# Main_uC.net
KiCad netlist of a schematic drawn in Altium Designer
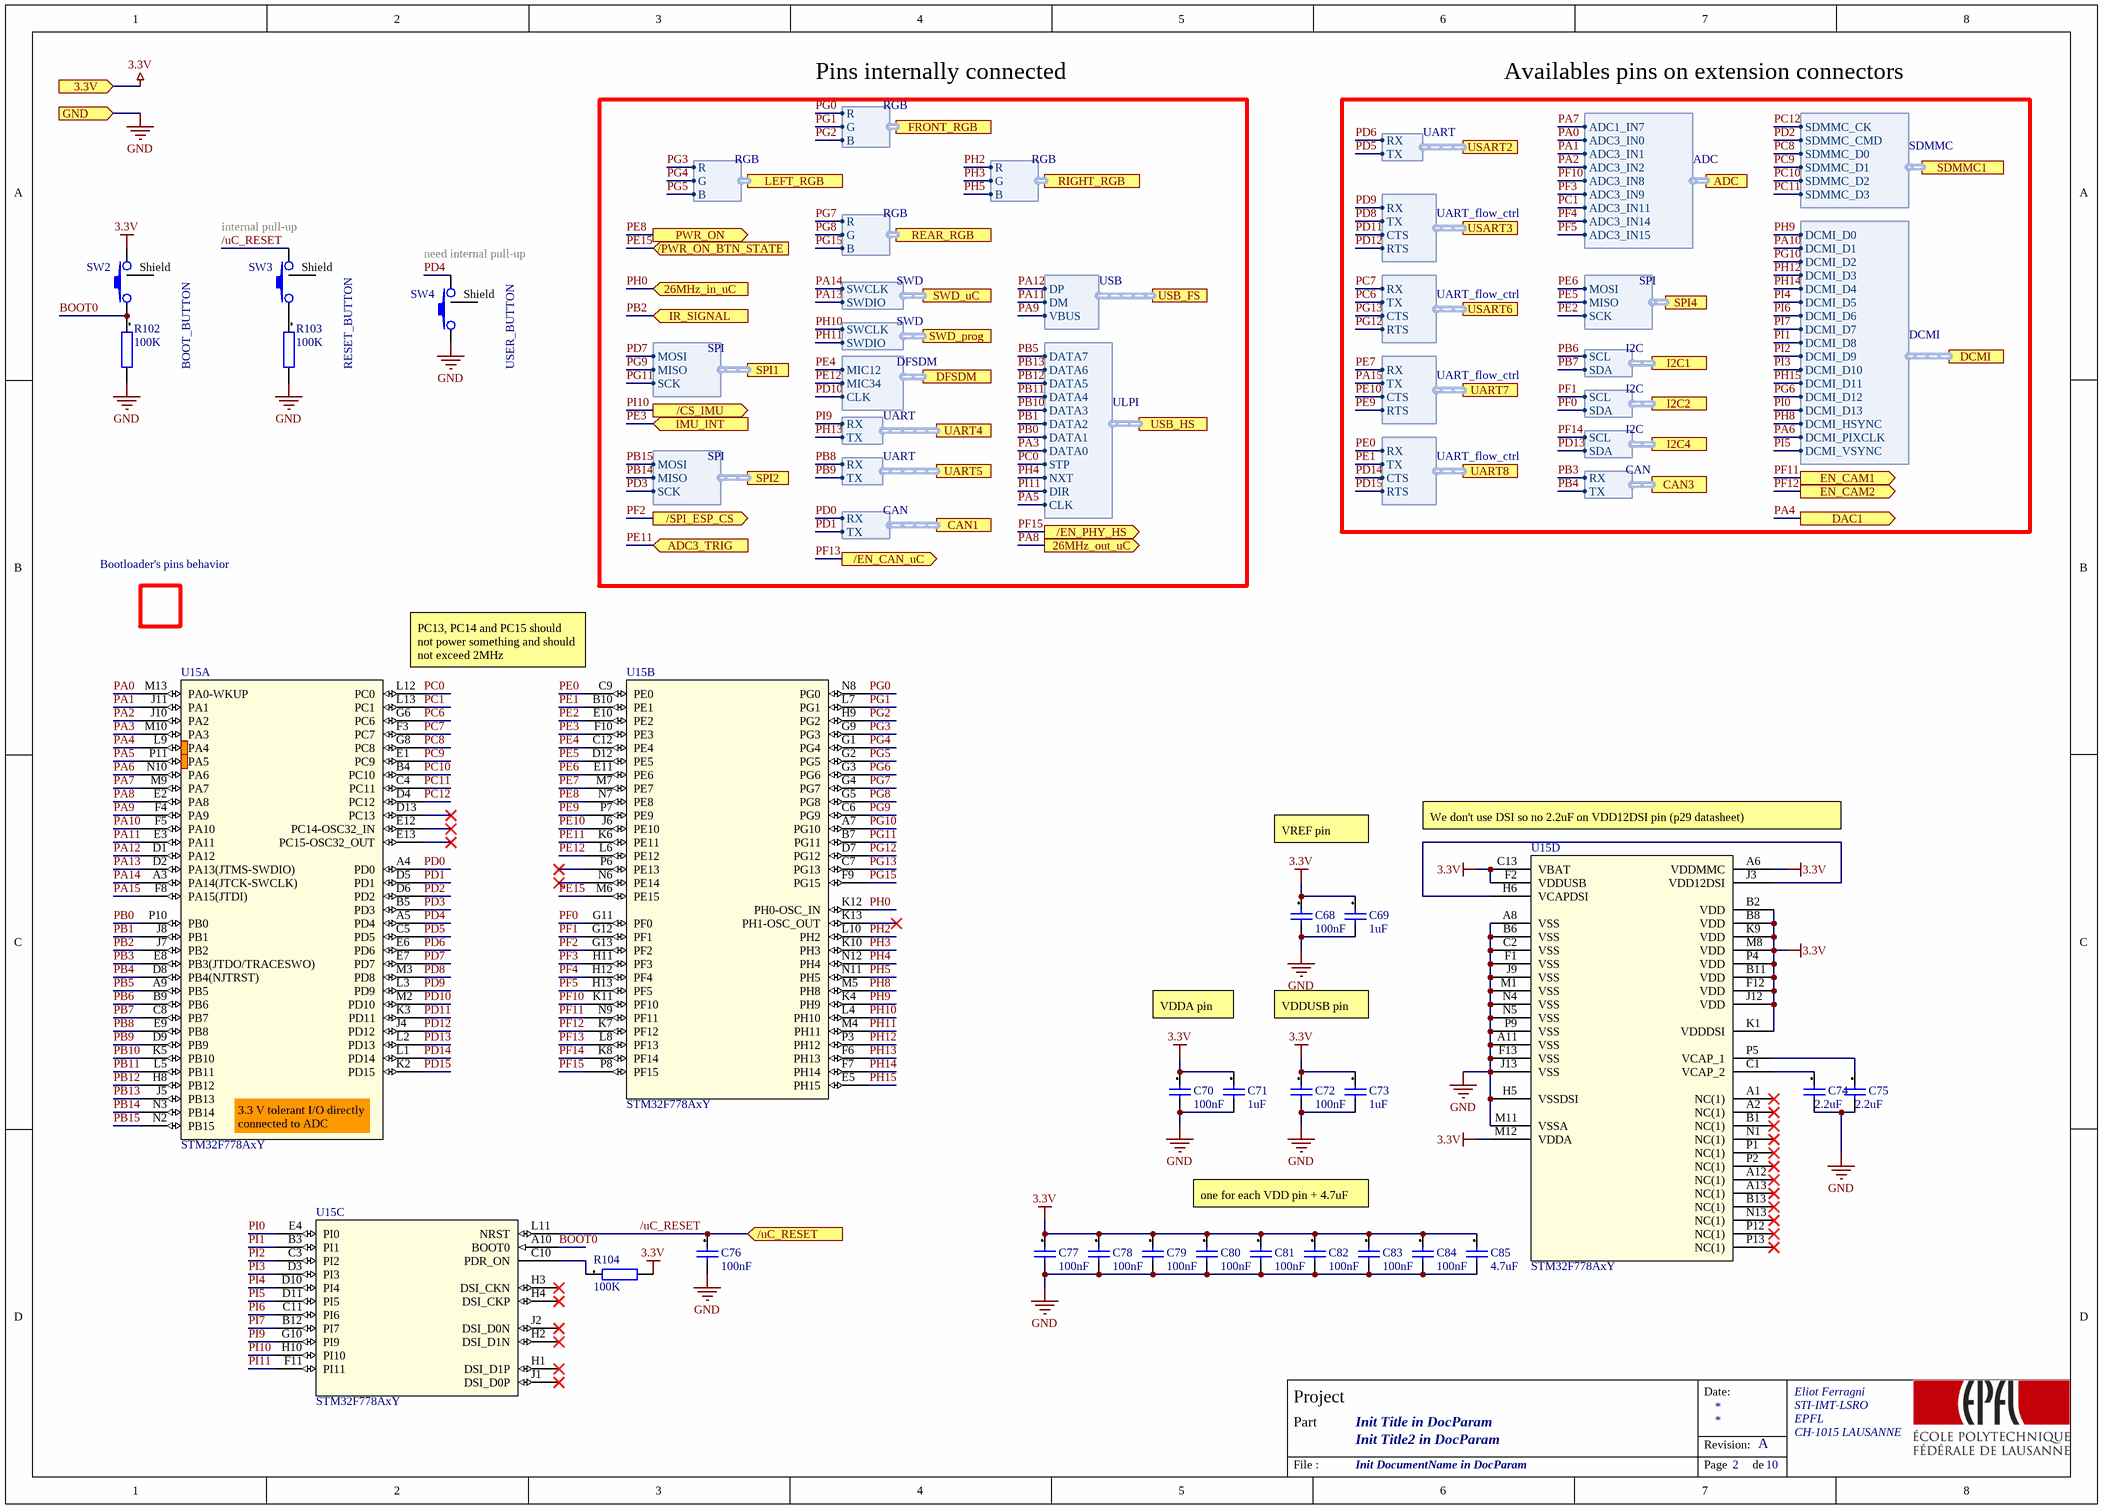
[diagram p0: Main_uC.SchDoc]

(export (version "E")
  (design (tool "Eeschema 10.0.6"))
  (components
    (comp (ref "C68")
      (value "100nF")
      (footprint "CAPC0201(0603)33_L")
      (description "Capacitor TBD 0201")
      (libsource (lib "LSRO1Altium") (part "CAP-NP"))
    )
    (comp (ref "C69")
      (value "1uF")
      (footprint "CAPC0201(0603)33_L")
      (description "Capacitor TBD 0201")
      (libsource (lib "LSRO1Altium") (part "CAP-NP"))
    )
    (comp (ref "C70")
      (value "100nF")
      (footprint "CAPC0201(0603)33_L")
      (description "Capacitor TBD 0201")
      (libsource (lib "LSRO1Altium") (part "CAP-NP"))
    )
    (comp (ref "C71")
      (value "1uF")
      (footprint "CAPC0201(0603)33_L")
      (description "Capacitor TBD 0201")
      (libsource (lib "LSRO1Altium") (part "CAP-NP"))
    )
    (comp (ref "C72")
      (value "100nF")
      (footprint "CAPC0201(0603)33_L")
      (description "Capacitor TBD 0201")
      (libsource (lib "LSRO1Altium") (part "CAP-NP"))
    )
    (comp (ref "C73")
      (value "1uF")
      (footprint "CAPC0201(0603)33_L")
      (description "Capacitor TBD 0201")
      (libsource (lib "LSRO1Altium") (part "CAP-NP"))
    )
    (comp (ref "C74")
      (value "2.2uF")
      (footprint "CAPC0201(0603)33_L")
      (description "Capacitor TBD 0201")
      (libsource (lib "LSRO1Altium") (part "CAP-NP"))
    )
    (comp (ref "C75")
      (value "2.2uF")
      (footprint "CAPC0201(0603)33_L")
      (description "Capacitor TBD 0201")
      (libsource (lib "LSRO1Altium") (part "CAP-NP"))
    )
    (comp (ref "C76")
      (value "100nF")
      (footprint "CAPC0201(0603)33_L")
      (description "Capacitor TBD 0201")
      (libsource (lib "LSRO1Altium") (part "CAP-NP"))
    )
    (comp (ref "C77")
      (value "100nF")
      (footprint "CAPC0201(0603)33_L")
      (description "Capacitor TBD 0201")
      (libsource (lib "LSRO1Altium") (part "CAP-NP"))
    )
    (comp (ref "C78")
      (value "100nF")
      (footprint "CAPC0201(0603)33_L")
      (description "Capacitor TBD 0201")
      (libsource (lib "LSRO1Altium") (part "CAP-NP"))
    )
    (comp (ref "C79")
      (value "100nF")
      (footprint "CAPC0201(0603)33_L")
      (description "Capacitor TBD 0201")
      (libsource (lib "LSRO1Altium") (part "CAP-NP"))
    )
    (comp (ref "C80")
      (value "100nF")
      (footprint "CAPC0201(0603)33_L")
      (description "Capacitor TBD 0201")
      (libsource (lib "LSRO1Altium") (part "CAP-NP"))
    )
    (comp (ref "C81")
      (value "100nF")
      (footprint "CAPC0201(0603)33_L")
      (description "Capacitor TBD 0201")
      (libsource (lib "LSRO1Altium") (part "CAP-NP"))
    )
    (comp (ref "C82")
      (value "100nF")
      (footprint "CAPC0201(0603)33_L")
      (description "Capacitor TBD 0201")
      (libsource (lib "LSRO1Altium") (part "CAP-NP"))
    )
    (comp (ref "C83")
      (value "100nF")
      (footprint "CAPC0201(0603)33_L")
      (description "Capacitor TBD 0201")
      (libsource (lib "LSRO1Altium") (part "CAP-NP"))
    )
    (comp (ref "C84")
      (value "100nF")
      (footprint "CAPC0201(0603)33_L")
      (description "Capacitor TBD 0201")
      (libsource (lib "LSRO1Altium") (part "CAP-NP"))
    )
    (comp (ref "C85")
      (value "4.7uF")
      (footprint "CAPC0201(0603)33_L")
      (description "Capacitor TBD 0201")
      (libsource (lib "LSRO1Altium") (part "CAP-NP"))
    )
    (comp (ref "R102")
      (value "100K")
      (footprint "RESC0201(0603)_L")
      (description "Resistor ToDo 0201")
      (libsource (lib "LSRO1Altium") (part "RES"))
    )
    (comp (ref "R103")
      (value "100K")
      (footprint "RESC0201(0603)_L")
      (description "Resistor ToDo 0201")
      (libsource (lib "LSRO1Altium") (part "RES"))
    )
    (comp (ref "R104")
      (value "100K")
      (footprint "RESC0201(0603)_L")
      (description "Resistor ToDo 0201")
      (libsource (lib "LSRO1Altium") (part "RES"))
    )
    (comp (ref "SW2")
      (value "button")
      (footprint "C&K_KMR2")
      (description "KMR221GLFS")
      (fields (field (name "MANUFACTURER") "Tyco"))
      (libsource (lib "Schlib") (part "C&K KMR2"))
    )
    (comp (ref "SW3")
      (value "button")
      (footprint "C&K_KMR2")
      (description "KMR221GLFS")
      (fields (field (name "MANUFACTURER") "Tyco"))
      (libsource (lib "Schlib") (part "C&K KMR2"))
    )
    (comp (ref "SW4")
      (value "button")
      (footprint "C&K_KMR2")
      (description "KMR221GLFS")
      (fields (field (name "MANUFACTURER") "Tyco"))
      (libsource (lib "Schlib") (part "C&K KMR2"))
    )
    (comp (ref "U15")
      (value "STM32F778AxY")
      (footprint "WLCSP-180")
      (description "Imported")
      (fields
        (field (name "MANUFACTURER_PART_NUMBER") "stm32f77xaxy")
        (field (name "COPYRIGHT") "Copyright (C) 2016 Accelerated Designs. All rights reserved")
      )
      (libsource (lib "Schlib") (part "STM32F77XAXY"))
    )
  )
  (nets
    (net (code "14") (name "/BOOT0") (class "Default")
      (node (ref "R102") (pin "1") (pinfunction "1_1") (pintype "passive"))
      (node (ref "SW2") (pin "1") (pintype "passive"))
      (node (ref "U15") (pin "A10") (pinfunction "BOOT0_A10") (pintype "input"))
    )
    (net (code "16") (name "/PA0") (class "Default")
      (node (ref "U15") (pin "M13") (pinfunction "PA0-WKUP_M13") (pintype "bidirectional"))
    )
    (net (code "17") (name "/PA1") (class "Default")
      (node (ref "U15") (pin "J11") (pinfunction "PA1_J11") (pintype "bidirectional"))
    )
    (net (code "18") (name "/PA2") (class "Default")
      (node (ref "U15") (pin "J10") (pinfunction "PA2_J10") (pintype "bidirectional"))
    )
    (net (code "19") (name "/PA3") (class "Default")
      (node (ref "U15") (pin "M10") (pinfunction "PA3_M10") (pintype "bidirectional"))
    )
    (net (code "20") (name "/PA4") (class "Default")
      (node (ref "U15") (pin "L9") (pinfunction "PA4_L9") (pintype "bidirectional"))
    )
    (net (code "21") (name "/PA5") (class "Default")
      (node (ref "U15") (pin "P11") (pinfunction "PA5_P11") (pintype "bidirectional"))
    )
    (net (code "22") (name "/PA6") (class "Default")
      (node (ref "U15") (pin "N10") (pinfunction "PA6_N10") (pintype "bidirectional"))
    )
    (net (code "23") (name "/PA7") (class "Default")
      (node (ref "U15") (pin "M9") (pinfunction "PA7_M9") (pintype "bidirectional"))
    )
    (net (code "24") (name "/PA8") (class "Default")
      (node (ref "U15") (pin "E2") (pinfunction "PA8_E2") (pintype "bidirectional"))
    )
    (net (code "25") (name "/PA9") (class "Default")
      (node (ref "U15") (pin "F4") (pinfunction "PA9_F4") (pintype "bidirectional"))
    )
    (net (code "26") (name "/PA10") (class "Default")
      (node (ref "U15") (pin "F5") (pinfunction "PA10_F5") (pintype "bidirectional"))
    )
    (net (code "27") (name "/PA11") (class "Default")
      (node (ref "U15") (pin "E3") (pinfunction "PA11_E3") (pintype "bidirectional"))
    )
    (net (code "28") (name "/PA12") (class "Default")
      (node (ref "U15") (pin "D1") (pinfunction "PA12_D1") (pintype "bidirectional"))
    )
    (net (code "29") (name "/PA13") (class "Default")
      (node (ref "U15") (pin "D2") (pinfunction "PA13(JTMS-SWDIO)_D2") (pintype "bidirectional"))
    )
    (net (code "30") (name "/PA14") (class "Default")
      (node (ref "U15") (pin "A3") (pinfunction "PA14(JTCK-SWCLK)_A3") (pintype "bidirectional"))
    )
    (net (code "31") (name "/PA15") (class "Default")
      (node (ref "U15") (pin "F8") (pinfunction "PA15(JTDI)_F8") (pintype "bidirectional"))
    )
    (net (code "32") (name "/PB0") (class "Default")
      (node (ref "U15") (pin "P10") (pinfunction "PB0_P10") (pintype "bidirectional"))
    )
    (net (code "33") (name "/PB1") (class "Default")
      (node (ref "U15") (pin "J8") (pinfunction "PB1_J8") (pintype "bidirectional"))
    )
    (net (code "34") (name "/PB2") (class "Default")
      (node (ref "U15") (pin "J7") (pinfunction "PB2_J7") (pintype "bidirectional"))
    )
    (net (code "35") (name "/PB3") (class "Default")
      (node (ref "U15") (pin "E8") (pinfunction "PB3(JTDO/TRACESWO)_E8") (pintype "bidirectional"))
    )
    (net (code "36") (name "/PB4") (class "Default")
      (node (ref "U15") (pin "D8") (pinfunction "PB4(NJTRST)_D8") (pintype "bidirectional"))
    )
    (net (code "37") (name "/PB5") (class "Default")
      (node (ref "U15") (pin "A9") (pinfunction "PB5_A9") (pintype "bidirectional"))
    )
    (net (code "38") (name "/PB6") (class "Default")
      (node (ref "U15") (pin "B9") (pinfunction "PB6_B9") (pintype "bidirectional"))
    )
    (net (code "39") (name "/PB7") (class "Default")
      (node (ref "U15") (pin "C8") (pinfunction "PB7_C8") (pintype "bidirectional"))
    )
    (net (code "40") (name "/PB8") (class "Default")
      (node (ref "U15") (pin "E9") (pinfunction "PB8_E9") (pintype "bidirectional"))
    )
    (net (code "41") (name "/PB9") (class "Default")
      (node (ref "U15") (pin "D9") (pinfunction "PB9_D9") (pintype "bidirectional"))
    )
    (net (code "42") (name "/PB10") (class "Default")
      (node (ref "U15") (pin "K5") (pinfunction "PB10_K5") (pintype "bidirectional"))
    )
    (net (code "43") (name "/PB11") (class "Default")
      (node (ref "U15") (pin "L5") (pinfunction "PB11_L5") (pintype "bidirectional"))
    )
    (net (code "44") (name "/PB12") (class "Default")
      (node (ref "U15") (pin "H8") (pinfunction "PB12_H8") (pintype "bidirectional"))
    )
    (net (code "45") (name "/PB13") (class "Default")
      (node (ref "U15") (pin "J5") (pinfunction "PB13_J5") (pintype "bidirectional"))
    )
    (net (code "46") (name "/PB14") (class "Default")
      (node (ref "U15") (pin "N3") (pinfunction "PB14_N3") (pintype "bidirectional"))
    )
    (net (code "47") (name "/PB15") (class "Default")
      (node (ref "U15") (pin "N2") (pinfunction "PB15_N2") (pintype "bidirectional"))
    )
    (net (code "48") (name "/PC0") (class "Default")
      (node (ref "U15") (pin "L12") (pinfunction "PC0_L12") (pintype "bidirectional"))
    )
    (net (code "49") (name "/PC1") (class "Default")
      (node (ref "U15") (pin "L13") (pinfunction "PC1_L13") (pintype "bidirectional"))
    )
    (net (code "50") (name "/PC6") (class "Default")
      (node (ref "U15") (pin "G6") (pinfunction "PC6_G6") (pintype "bidirectional"))
    )
    (net (code "51") (name "/PC7") (class "Default")
      (node (ref "U15") (pin "F3") (pinfunction "PC7_F3") (pintype "bidirectional"))
    )
    (net (code "52") (name "/PC8") (class "Default")
      (node (ref "U15") (pin "G8") (pinfunction "PC8_G8") (pintype "bidirectional"))
    )
    (net (code "53") (name "/PC9") (class "Default")
      (node (ref "U15") (pin "E1") (pinfunction "PC9_E1") (pintype "bidirectional"))
    )
    (net (code "54") (name "/PC10") (class "Default")
      (node (ref "U15") (pin "B4") (pinfunction "PC10_B4") (pintype "bidirectional"))
    )
    (net (code "55") (name "/PC11") (class "Default")
      (node (ref "U15") (pin "C4") (pinfunction "PC11_C4") (pintype "bidirectional"))
    )
    (net (code "56") (name "/PC12") (class "Default")
      (node (ref "U15") (pin "D4") (pinfunction "PC12_D4") (pintype "bidirectional"))
    )
    (net (code "57") (name "/PD0") (class "Default")
      (node (ref "U15") (pin "A4") (pinfunction "PD0_A4") (pintype "bidirectional"))
    )
    (net (code "58") (name "/PD1") (class "Default")
      (node (ref "U15") (pin "D5") (pinfunction "PD1_D5") (pintype "bidirectional"))
    )
    (net (code "59") (name "/PD2") (class "Default")
      (node (ref "U15") (pin "D6") (pinfunction "PD2_D6") (pintype "bidirectional"))
    )
    (net (code "60") (name "/PD3") (class "Default")
      (node (ref "U15") (pin "B5") (pinfunction "PD3_B5") (pintype "bidirectional"))
    )
    (net (code "61") (name "/PD4") (class "Default")
      (node (ref "SW4") (pin "2") (pintype "passive"))
      (node (ref "U15") (pin "A5") (pinfunction "PD4_A5") (pintype "bidirectional"))
    )
    (net (code "62") (name "/PD5") (class "Default")
      (node (ref "U15") (pin "C5") (pinfunction "PD5_C5") (pintype "bidirectional"))
    )
    (net (code "63") (name "/PD6") (class "Default")
      (node (ref "U15") (pin "E6") (pinfunction "PD6_E6") (pintype "bidirectional"))
    )
    (net (code "64") (name "/PD7") (class "Default")
      (node (ref "U15") (pin "E7") (pinfunction "PD7_E7") (pintype "bidirectional"))
    )
    (net (code "65") (name "/PD8") (class "Default")
      (node (ref "U15") (pin "M3") (pinfunction "PD8_M3") (pintype "bidirectional"))
    )
    (net (code "66") (name "/PD9") (class "Default")
      (node (ref "U15") (pin "L3") (pinfunction "PD9_L3") (pintype "bidirectional"))
    )
    (net (code "67") (name "/PD10") (class "Default")
      (node (ref "U15") (pin "M2") (pinfunction "PD10_M2") (pintype "bidirectional"))
    )
    (net (code "68") (name "/PD11") (class "Default")
      (node (ref "U15") (pin "K3") (pinfunction "PD11_K3") (pintype "bidirectional"))
    )
    (net (code "69") (name "/PD12") (class "Default")
      (node (ref "U15") (pin "J4") (pinfunction "PD12_J4") (pintype "bidirectional"))
    )
    (net (code "70") (name "/PD13") (class "Default")
      (node (ref "U15") (pin "L2") (pinfunction "PD13_L2") (pintype "bidirectional"))
    )
    (net (code "71") (name "/PD14") (class "Default")
      (node (ref "U15") (pin "L1") (pinfunction "PD14_L1") (pintype "bidirectional"))
    )
    (net (code "72") (name "/PD15") (class "Default")
      (node (ref "U15") (pin "K2") (pinfunction "PD15_K2") (pintype "bidirectional"))
    )
    (net (code "73") (name "/PE0") (class "Default")
      (node (ref "U15") (pin "C9") (pinfunction "PE0_C9") (pintype "bidirectional"))
    )
    (net (code "74") (name "/PE1") (class "Default")
      (node (ref "U15") (pin "B10") (pinfunction "PE1_B10") (pintype "bidirectional"))
    )
    (net (code "75") (name "/PE2") (class "Default")
      (node (ref "U15") (pin "E10") (pinfunction "PE2_E10") (pintype "bidirectional"))
    )
    (net (code "76") (name "/PE3") (class "Default")
      (node (ref "U15") (pin "F10") (pinfunction "PE3_F10") (pintype "bidirectional"))
    )
    (net (code "77") (name "/PE4") (class "Default")
      (node (ref "U15") (pin "C12") (pinfunction "PE4_C12") (pintype "bidirectional"))
    )
    (net (code "78") (name "/PE5") (class "Default")
      (node (ref "U15") (pin "D12") (pinfunction "PE5_D12") (pintype "bidirectional"))
    )
    (net (code "79") (name "/PE6") (class "Default")
      (node (ref "U15") (pin "E11") (pinfunction "PE6_E11") (pintype "bidirectional"))
    )
    (net (code "80") (name "/PE7") (class "Default")
      (node (ref "U15") (pin "M7") (pinfunction "PE7_M7") (pintype "bidirectional"))
    )
    (net (code "81") (name "/PE8") (class "Default")
      (node (ref "U15") (pin "N7") (pinfunction "PE8_N7") (pintype "bidirectional"))
    )
    (net (code "82") (name "/PE9") (class "Default")
      (node (ref "U15") (pin "P7") (pinfunction "PE9_P7") (pintype "bidirectional"))
    )
    (net (code "83") (name "/PE10") (class "Default")
      (node (ref "U15") (pin "J6") (pinfunction "PE10_J6") (pintype "bidirectional"))
    )
    (net (code "84") (name "/PE11") (class "Default")
      (node (ref "U15") (pin "K6") (pinfunction "PE11_K6") (pintype "bidirectional"))
    )
    (net (code "85") (name "/PE12") (class "Default")
      (node (ref "U15") (pin "L6") (pinfunction "PE12_L6") (pintype "bidirectional"))
    )
    (net (code "86") (name "/PE15") (class "Default")
      (node (ref "U15") (pin "M6") (pinfunction "PE15_M6") (pintype "bidirectional"))
    )
    (net (code "87") (name "/PF0") (class "Default")
      (node (ref "U15") (pin "G11") (pinfunction "PF0_G11") (pintype "bidirectional"))
    )
    (net (code "88") (name "/PF1") (class "Default")
      (node (ref "U15") (pin "G12") (pinfunction "PF1_G12") (pintype "bidirectional"))
    )
    (net (code "89") (name "/PF2") (class "Default")
      (node (ref "U15") (pin "G13") (pinfunction "PF2_G13") (pintype "bidirectional"))
    )
    (net (code "90") (name "/PF3") (class "Default")
      (node (ref "U15") (pin "H11") (pinfunction "PF3_H11") (pintype "bidirectional"))
    )
    (net (code "91") (name "/PF4") (class "Default")
      (node (ref "U15") (pin "H12") (pinfunction "PF4_H12") (pintype "bidirectional"))
    )
    (net (code "92") (name "/PF5") (class "Default")
      (node (ref "U15") (pin "H13") (pinfunction "PF5_H13") (pintype "bidirectional"))
    )
    (net (code "93") (name "/PF10") (class "Default")
      (node (ref "U15") (pin "K11") (pinfunction "PF10_K11") (pintype "bidirectional"))
    )
    (net (code "94") (name "/PF11") (class "Default")
      (node (ref "U15") (pin "N9") (pinfunction "PF11_N9") (pintype "bidirectional"))
    )
    (net (code "95") (name "/PF12") (class "Default")
      (node (ref "U15") (pin "K7") (pinfunction "PF12_K7") (pintype "bidirectional"))
    )
    (net (code "96") (name "/PF13") (class "Default")
      (node (ref "U15") (pin "L8") (pinfunction "PF13_L8") (pintype "bidirectional"))
    )
    (net (code "97") (name "/PF14") (class "Default")
      (node (ref "U15") (pin "K8") (pinfunction "PF14_K8") (pintype "bidirectional"))
    )
    (net (code "98") (name "/PF15") (class "Default")
      (node (ref "U15") (pin "P8") (pinfunction "PF15_P8") (pintype "bidirectional"))
    )
    (net (code "99") (name "/PG0") (class "Default")
      (node (ref "U15") (pin "N8") (pinfunction "PG0_N8") (pintype "bidirectional"))
    )
    (net (code "100") (name "/PG1") (class "Default")
      (node (ref "U15") (pin "L7") (pinfunction "PG1_L7") (pintype "bidirectional"))
    )
    (net (code "101") (name "/PG2") (class "Default")
      (node (ref "U15") (pin "H9") (pinfunction "PG2_H9") (pintype "bidirectional"))
    )
    (net (code "102") (name "/PG3") (class "Default")
      (node (ref "U15") (pin "G9") (pinfunction "PG3_G9") (pintype "bidirectional"))
    )
    (net (code "103") (name "/PG4") (class "Default")
      (node (ref "U15") (pin "G1") (pinfunction "PG4_G1") (pintype "bidirectional"))
    )
    (net (code "104") (name "/PG5") (class "Default")
      (node (ref "U15") (pin "G2") (pinfunction "PG5_G2") (pintype "bidirectional"))
    )
    (net (code "105") (name "/PG6") (class "Default")
      (node (ref "U15") (pin "G3") (pinfunction "PG6_G3") (pintype "bidirectional"))
    )
    (net (code "106") (name "/PG7") (class "Default")
      (node (ref "U15") (pin "G4") (pinfunction "PG7_G4") (pintype "bidirectional"))
    )
    (net (code "107") (name "/PG8") (class "Default")
      (node (ref "U15") (pin "G5") (pinfunction "PG8_G5") (pintype "bidirectional"))
    )
    (net (code "108") (name "/PG9") (class "Default")
      (node (ref "U15") (pin "C6") (pinfunction "PG9_C6") (pintype "bidirectional"))
    )
    (net (code "109") (name "/PG10") (class "Default")
      (node (ref "U15") (pin "A7") (pinfunction "PG10_A7") (pintype "bidirectional"))
    )
    (net (code "110") (name "/PG11") (class "Default")
      (node (ref "U15") (pin "B7") (pinfunction "PG11_B7") (pintype "bidirectional"))
    )
    (net (code "111") (name "/PG12") (class "Default")
      (node (ref "U15") (pin "D7") (pinfunction "PG12_D7") (pintype "bidirectional"))
    )
    (net (code "112") (name "/PG13") (class "Default")
      (node (ref "U15") (pin "C7") (pinfunction "PG13_C7") (pintype "bidirectional"))
    )
    (net (code "113") (name "/PG15") (class "Default")
      (node (ref "U15") (pin "F9") (pinfunction "PG15_F9") (pintype "bidirectional"))
    )
    (net (code "114") (name "/PH0") (class "Default")
      (node (ref "U15") (pin "K12") (pinfunction "PH0-OSC_IN_K12") (pintype "bidirectional"))
    )
    (net (code "115") (name "/PH2") (class "Default")
      (node (ref "U15") (pin "L10") (pinfunction "PH2_L10") (pintype "bidirectional"))
    )
    (net (code "116") (name "/PH3") (class "Default")
      (node (ref "U15") (pin "K10") (pinfunction "PH3_K10") (pintype "bidirectional"))
    )
    (net (code "117") (name "/PH4") (class "Default")
      (node (ref "U15") (pin "N12") (pinfunction "PH4_N12") (pintype "bidirectional"))
    )
    (net (code "118") (name "/PH5") (class "Default")
      (node (ref "U15") (pin "N11") (pinfunction "PH5_N11") (pintype "bidirectional"))
    )
    (net (code "119") (name "/PH8") (class "Default")
      (node (ref "U15") (pin "M5") (pinfunction "PH8_M5") (pintype "bidirectional"))
    )
    (net (code "120") (name "/PH9") (class "Default")
      (node (ref "U15") (pin "K4") (pinfunction "PH9_K4") (pintype "bidirectional"))
    )
    (net (code "121") (name "/PH10") (class "Default")
      (node (ref "U15") (pin "L4") (pinfunction "PH10_L4") (pintype "bidirectional"))
    )
    (net (code "122") (name "/PH11") (class "Default")
      (node (ref "U15") (pin "M4") (pinfunction "PH11_M4") (pintype "bidirectional"))
    )
    (net (code "123") (name "/PH12") (class "Default")
      (node (ref "U15") (pin "P3") (pinfunction "PH12_P3") (pintype "bidirectional"))
    )
    (net (code "124") (name "/PH13") (class "Default")
      (node (ref "U15") (pin "F6") (pinfunction "PH13_F6") (pintype "bidirectional"))
    )
    (net (code "125") (name "/PH14") (class "Default")
      (node (ref "U15") (pin "F7") (pinfunction "PH14_F7") (pintype "bidirectional"))
    )
    (net (code "126") (name "/PH15") (class "Default")
      (node (ref "U15") (pin "E5") (pinfunction "PH15_E5") (pintype "bidirectional"))
    )
    (net (code "127") (name "/PI0") (class "Default")
      (node (ref "U15") (pin "E4") (pinfunction "PI0_E4") (pintype "bidirectional"))
    )
    (net (code "128") (name "/PI1") (class "Default")
      (node (ref "U15") (pin "B3") (pinfunction "PI1_B3") (pintype "bidirectional"))
    )
    (net (code "129") (name "/PI2") (class "Default")
      (node (ref "U15") (pin "C3") (pinfunction "PI2_C3") (pintype "bidirectional"))
    )
    (net (code "130") (name "/PI3") (class "Default")
      (node (ref "U15") (pin "D3") (pinfunction "PI3_D3") (pintype "bidirectional"))
    )
    (net (code "131") (name "/PI4") (class "Default")
      (node (ref "U15") (pin "D10") (pinfunction "PI4_D10") (pintype "bidirectional"))
    )
    (net (code "132") (name "/PI5") (class "Default")
      (node (ref "U15") (pin "D11") (pinfunction "PI5_D11") (pintype "bidirectional"))
    )
    (net (code "133") (name "/PI6") (class "Default")
      (node (ref "U15") (pin "C11") (pinfunction "PI6_C11") (pintype "bidirectional"))
    )
    (net (code "134") (name "/PI7") (class "Default")
      (node (ref "U15") (pin "B12") (pinfunction "PI7_B12") (pintype "bidirectional"))
    )
    (net (code "135") (name "/PI9") (class "Default")
      (node (ref "U15") (pin "G10") (pinfunction "PI9_G10") (pintype "bidirectional"))
    )
    (net (code "136") (name "/PI10") (class "Default")
      (node (ref "U15") (pin "H10") (pinfunction "PI10_H10") (pintype "bidirectional"))
    )
    (net (code "137") (name "/PI11") (class "Default")
      (node (ref "U15") (pin "F11") (pinfunction "PI11_F11") (pintype "bidirectional"))
    )
    (net (code "150") (name "/{slash}uC_RESET") (class "Default")
      (node (ref "C76") (pin "1") (pinfunction "1_1") (pintype "passive"))
      (node (ref "SW3") (pin "2") (pintype "passive"))
      (node (ref "U15") (pin "L11") (pinfunction "NRST_L11") (pintype "bidirectional"))
    )
    (net (code "151") (name "3.3V") (class "Default")
      (node (ref "C68") (pin "1") (pinfunction "1_1") (pintype "passive"))
      (node (ref "C69") (pin "1") (pinfunction "1_1") (pintype "passive"))
      (node (ref "C70") (pin "1") (pinfunction "1_1") (pintype "passive"))
      (node (ref "C71") (pin "1") (pinfunction "1_1") (pintype "passive"))
      (node (ref "C72") (pin "1") (pinfunction "1_1") (pintype "passive"))
      (node (ref "C73") (pin "1") (pinfunction "1_1") (pintype "passive"))
      (node (ref "C77") (pin "1") (pinfunction "1_1") (pintype "passive"))
      (node (ref "C78") (pin "1") (pinfunction "1_1") (pintype "passive"))
      (node (ref "C79") (pin "1") (pinfunction "1_1") (pintype "passive"))
      (node (ref "C80") (pin "1") (pinfunction "1_1") (pintype "passive"))
      (node (ref "C81") (pin "1") (pinfunction "1_1") (pintype "passive"))
      (node (ref "C82") (pin "1") (pinfunction "1_1") (pintype "passive"))
      (node (ref "C83") (pin "1") (pinfunction "1_1") (pintype "passive"))
      (node (ref "C84") (pin "1") (pinfunction "1_1") (pintype "passive"))
      (node (ref "C85") (pin "1") (pinfunction "1_1") (pintype "passive"))
      (node (ref "R104") (pin "2") (pinfunction "2_2") (pintype "passive"))
      (node (ref "SW2") (pin "2") (pintype "passive"))
      (node (ref "U15") (pin "A6") (pinfunction "VDDMMC_A6") (pintype "power_in"))
      (node (ref "U15") (pin "B11") (pinfunction "VDD_B11") (pintype "power_in"))
      (node (ref "U15") (pin "B2") (pinfunction "VDD_B2") (pintype "power_in"))
      (node (ref "U15") (pin "B8") (pinfunction "VDD_B8") (pintype "power_in"))
      (node (ref "U15") (pin "C13") (pinfunction "VBAT_C13") (pintype "power_in"))
      (node (ref "U15") (pin "F12") (pinfunction "VDD_F12") (pintype "power_in"))
      (node (ref "U15") (pin "F2") (pinfunction "VDDUSB_F2") (pintype "power_in"))
      (node (ref "U15") (pin "J12") (pinfunction "VDD_J12") (pintype "power_in"))
      (node (ref "U15") (pin "K1") (pinfunction "VDDDSI_K1") (pintype "power_in"))
      (node (ref "U15") (pin "K9") (pinfunction "VDD_K9") (pintype "power_in"))
      (node (ref "U15") (pin "M12") (pinfunction "VDDA_M12") (pintype "power_in"))
      (node (ref "U15") (pin "M8") (pinfunction "VDD_M8") (pintype "power_in"))
      (node (ref "U15") (pin "P4") (pinfunction "VDD_P4") (pintype "power_in"))
    )
    (net (code "152") (name "GND") (class "Default")
      (node (ref "C68") (pin "2") (pinfunction "2_2") (pintype "passive"))
      (node (ref "C69") (pin "2") (pinfunction "2_2") (pintype "passive"))
      (node (ref "C70") (pin "2") (pinfunction "2_2") (pintype "passive"))
      (node (ref "C71") (pin "2") (pinfunction "2_2") (pintype "passive"))
      (node (ref "C72") (pin "2") (pinfunction "2_2") (pintype "passive"))
      (node (ref "C73") (pin "2") (pinfunction "2_2") (pintype "passive"))
      (node (ref "C74") (pin "2") (pinfunction "2_2") (pintype "passive"))
      (node (ref "C75") (pin "2") (pinfunction "2_2") (pintype "passive"))
      (node (ref "C76") (pin "2") (pinfunction "2_2") (pintype "passive"))
      (node (ref "C77") (pin "2") (pinfunction "2_2") (pintype "passive"))
      (node (ref "C78") (pin "2") (pinfunction "2_2") (pintype "passive"))
      (node (ref "C79") (pin "2") (pinfunction "2_2") (pintype "passive"))
      (node (ref "C80") (pin "2") (pinfunction "2_2") (pintype "passive"))
      (node (ref "C81") (pin "2") (pinfunction "2_2") (pintype "passive"))
      (node (ref "C82") (pin "2") (pinfunction "2_2") (pintype "passive"))
      (node (ref "C83") (pin "2") (pinfunction "2_2") (pintype "passive"))
      (node (ref "C84") (pin "2") (pinfunction "2_2") (pintype "passive"))
      (node (ref "C85") (pin "2") (pinfunction "2_2") (pintype "passive"))
      (node (ref "R102") (pin "2") (pinfunction "2_2") (pintype "passive"))
      (node (ref "R103") (pin "2") (pinfunction "2_2") (pintype "passive"))
      (node (ref "SW4") (pin "1") (pintype "passive"))
      (node (ref "U15") (pin "A11") (pinfunction "VSS_A11") (pintype "power_in"))
      (node (ref "U15") (pin "A8") (pinfunction "VSS_A8") (pintype "power_in"))
      (node (ref "U15") (pin "B6") (pinfunction "VSS_B6") (pintype "power_in"))
      (node (ref "U15") (pin "C2") (pinfunction "VSS_C2") (pintype "power_in"))
      (node (ref "U15") (pin "F1") (pinfunction "VSS_F1") (pintype "power_in"))
      (node (ref "U15") (pin "F13") (pinfunction "VSS_F13") (pintype "power_in"))
      (node (ref "U15") (pin "H5") (pinfunction "VSSDSI_H5") (pintype "power_in"))
      (node (ref "U15") (pin "J13") (pinfunction "VSS_J13") (pintype "power_in"))
      (node (ref "U15") (pin "J9") (pinfunction "VSS_J9") (pintype "power_in"))
      (node (ref "U15") (pin "M1") (pinfunction "VSS_M1") (pintype "power_in"))
      (node (ref "U15") (pin "M11") (pinfunction "VSSA_M11") (pintype "power_in"))
      (node (ref "U15") (pin "N4") (pinfunction "VSS_N4") (pintype "power_in"))
      (node (ref "U15") (pin "N5") (pinfunction "VSS_N5") (pintype "power_in"))
      (node (ref "U15") (pin "P9") (pinfunction "VSS_P9") (pintype "power_in"))
    )
    (net (code "153") (name "Net-(R103-Pad1)") (class "Default")
      (node (ref "R103") (pin "1") (pinfunction "1_1") (pintype "passive"))
      (node (ref "SW3") (pin "1") (pintype "passive"))
    )
    (net (code "154") (name "Net-(U15C-PDR_ON)") (class "Default")
      (node (ref "R104") (pin "1") (pinfunction "1_1") (pintype "passive"))
      (node (ref "U15") (pin "C10") (pinfunction "PDR_ON_C10") (pintype "passive"))
    )
    (net (code "155") (name "Net-(U15D-VCAPDSI)") (class "Default")
      (node (ref "U15") (pin "H6") (pinfunction "VCAPDSI_H6") (pintype "power_in"))
      (node (ref "U15") (pin "J3") (pinfunction "VDD12DSI_J3") (pintype "power_in"))
    )
    (net (code "156") (name "Net-(U15D-VCAP_1)") (class "Default")
      (node (ref "C75") (pin "1") (pinfunction "1_1") (pintype "passive"))
      (node (ref "U15") (pin "P5") (pinfunction "VCAP_1_P5") (pintype "power_in"))
    )
    (net (code "157") (name "Net-(U15D-VCAP_2)") (class "Default")
      (node (ref "C74") (pin "1") (pinfunction "1_1") (pintype "passive"))
      (node (ref "U15") (pin "C1") (pinfunction "VCAP_2_C1") (pintype "power_in"))
    )
    (net (code "158") (name "unconnected-(SW2-PadShield)") (class "Default")
      (node (ref "SW2") (pin "Shield") (pinfunction "Shield_Shield") (pintype "passive"))
    )
    (net (code "159") (name "unconnected-(SW3-PadShield)") (class "Default")
      (node (ref "SW3") (pin "Shield") (pinfunction "Shield_Shield") (pintype "passive"))
    )
    (net (code "160") (name "unconnected-(SW4-PadShield)") (class "Default")
      (node (ref "SW4") (pin "Shield") (pinfunction "Shield_Shield") (pintype "passive"))
    )
    (net (code "161") (name "unconnected-(U15A-PC13-PadD13)") (class "Default")
      (node (ref "U15") (pin "D13") (pinfunction "PC13_D13") (pintype "bidirectional+no_connect"))
    )
    (net (code "162") (name "unconnected-(U15A-PC14-OSC32_IN-PadE12)") (class "Default")
      (node (ref "U15") (pin "E12") (pinfunction "PC14-OSC32_IN_E12") (pintype "bidirectional+no_connect"))
    )
    (net (code "163") (name "unconnected-(U15A-PC15-OSC32_OUT-PadE13)") (class "Default")
      (node (ref "U15") (pin "E13") (pinfunction "PC15-OSC32_OUT_E13") (pintype "bidirectional+no_connect"))
    )
    (net (code "164") (name "unconnected-(U15B-PE13-PadP6)") (class "Default")
      (node (ref "U15") (pin "P6") (pinfunction "PE13_P6") (pintype "bidirectional+no_connect"))
    )
    (net (code "165") (name "unconnected-(U15B-PE14-PadN6)") (class "Default")
      (node (ref "U15") (pin "N6") (pinfunction "PE14_N6") (pintype "bidirectional+no_connect"))
    )
    (net (code "166") (name "unconnected-(U15B-PH1-OSC_OUT-PadK13)") (class "Default")
      (node (ref "U15") (pin "K13") (pinfunction "PH1-OSC_OUT_K13") (pintype "bidirectional+no_connect"))
    )
    (net (code "167") (name "unconnected-(U15C-DSI_CKN-PadH3)") (class "Default")
      (node (ref "U15") (pin "H3") (pinfunction "DSI_CKN_H3") (pintype "bidirectional+no_connect"))
    )
    (net (code "168") (name "unconnected-(U15C-DSI_CKP-PadH4)") (class "Default")
      (node (ref "U15") (pin "H4") (pinfunction "DSI_CKP_H4") (pintype "bidirectional+no_connect"))
    )
    (net (code "169") (name "unconnected-(U15C-DSI_D0N-PadJ2)") (class "Default")
      (node (ref "U15") (pin "J2") (pinfunction "DSI_D0N_J2") (pintype "bidirectional+no_connect"))
    )
    (net (code "170") (name "unconnected-(U15C-DSI_D0P-PadJ1)") (class "Default")
      (node (ref "U15") (pin "J1") (pinfunction "DSI_D0P_J1") (pintype "bidirectional+no_connect"))
    )
    (net (code "171") (name "unconnected-(U15C-DSI_D1N-PadH2)") (class "Default")
      (node (ref "U15") (pin "H2") (pinfunction "DSI_D1N_H2") (pintype "bidirectional+no_connect"))
    )
    (net (code "172") (name "unconnected-(U15C-DSI_D1P-PadH1)") (class "Default")
      (node (ref "U15") (pin "H1") (pinfunction "DSI_D1P_H1") (pintype "bidirectional+no_connect"))
    )
    (net (code "173") (name "unconnected-(U15D-NC(1)-PadA1)") (class "Default")
      (node (ref "U15") (pin "A1") (pinfunction "NC(1)_A1") (pintype "passive+no_connect"))
    )
    (net (code "174") (name "unconnected-(U15D-NC(1)-PadA2)") (class "Default")
      (node (ref "U15") (pin "A2") (pinfunction "NC(1)_A2") (pintype "passive+no_connect"))
    )
    (net (code "175") (name "unconnected-(U15D-NC(1)-PadA12)") (class "Default")
      (node (ref "U15") (pin "A12") (pinfunction "NC(1)_A12") (pintype "passive+no_connect"))
    )
    (net (code "176") (name "unconnected-(U15D-NC(1)-PadA13)") (class "Default")
      (node (ref "U15") (pin "A13") (pinfunction "NC(1)_A13") (pintype "passive+no_connect"))
    )
    (net (code "177") (name "unconnected-(U15D-NC(1)-PadB1)") (class "Default")
      (node (ref "U15") (pin "B1") (pinfunction "NC(1)_B1") (pintype "passive+no_connect"))
    )
    (net (code "178") (name "unconnected-(U15D-NC(1)-PadB13)") (class "Default")
      (node (ref "U15") (pin "B13") (pinfunction "NC(1)_B13") (pintype "passive+no_connect"))
    )
    (net (code "179") (name "unconnected-(U15D-NC(1)-PadN1)") (class "Default")
      (node (ref "U15") (pin "N1") (pinfunction "NC(1)_N1") (pintype "passive+no_connect"))
    )
    (net (code "180") (name "unconnected-(U15D-NC(1)-PadN13)") (class "Default")
      (node (ref "U15") (pin "N13") (pinfunction "NC(1)_N13") (pintype "passive+no_connect"))
    )
    (net (code "181") (name "unconnected-(U15D-NC(1)-PadP1)") (class "Default")
      (node (ref "U15") (pin "P1") (pinfunction "NC(1)_P1") (pintype "passive+no_connect"))
    )
    (net (code "182") (name "unconnected-(U15D-NC(1)-PadP2)") (class "Default")
      (node (ref "U15") (pin "P2") (pinfunction "NC(1)_P2") (pintype "passive+no_connect"))
    )
    (net (code "183") (name "unconnected-(U15D-NC(1)-PadP12)") (class "Default")
      (node (ref "U15") (pin "P12") (pinfunction "NC(1)_P12") (pintype "passive+no_connect"))
    )
    (net (code "184") (name "unconnected-(U15D-NC(1)-PadP13)") (class "Default")
      (node (ref "U15") (pin "P13") (pinfunction "NC(1)_P13") (pintype "passive+no_connect"))
    )
  )
)
